# FT2232D.net
KiCad netlist of a schematic drawn in Altium Designer
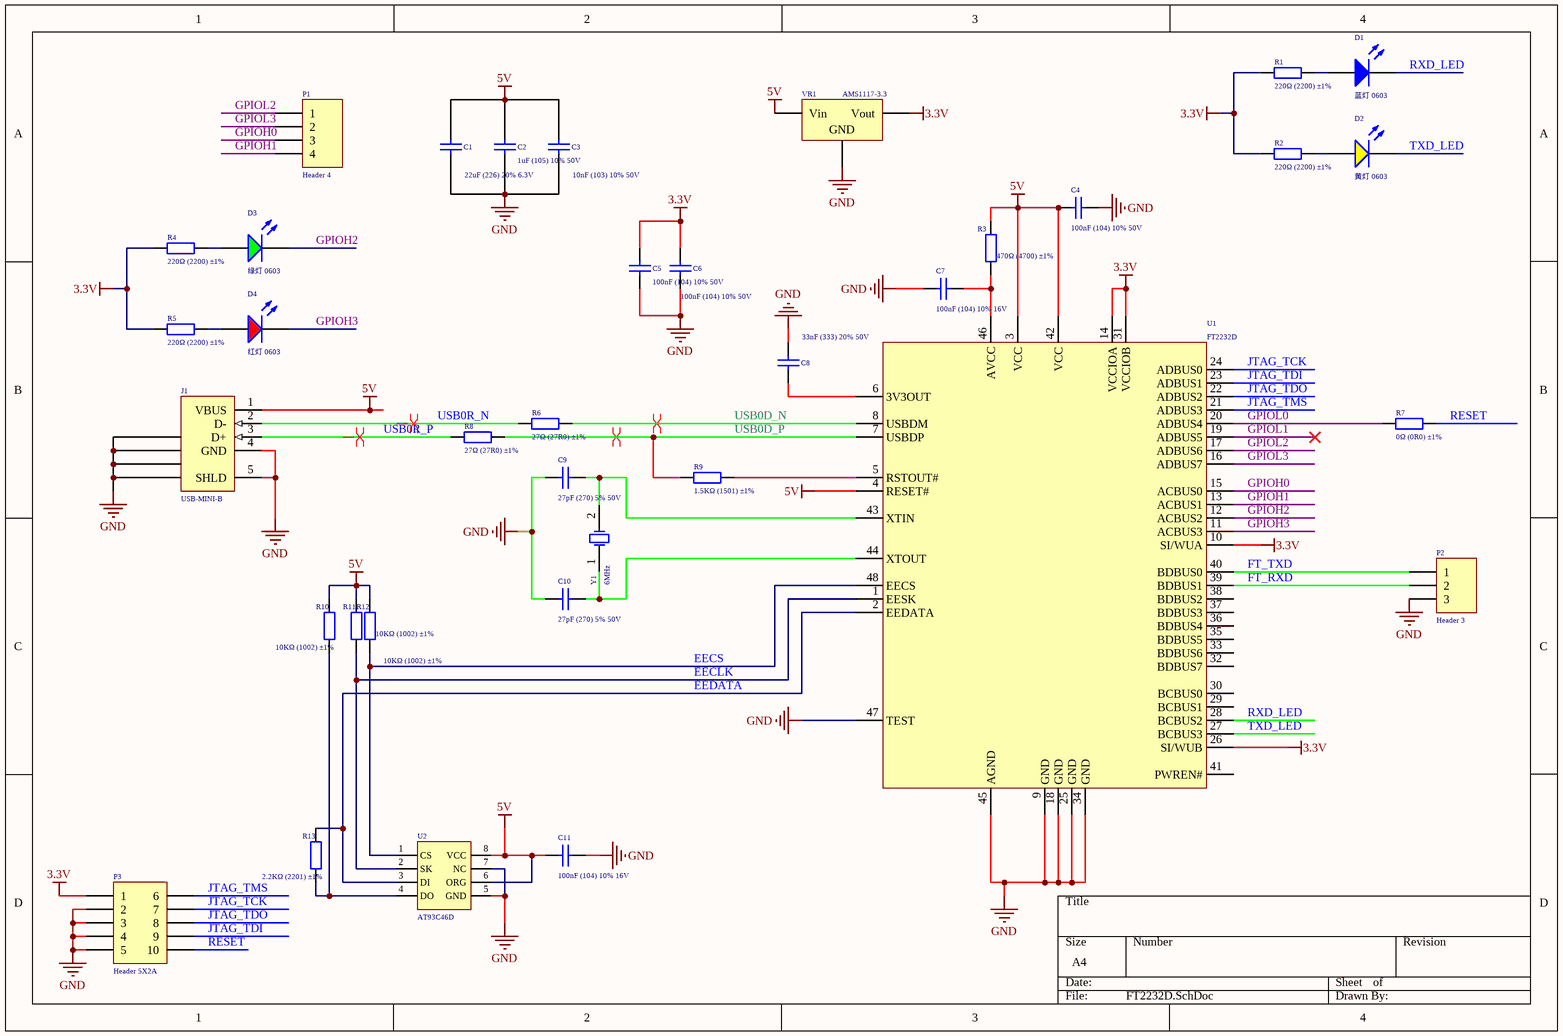
[diagram p0: FT2232D.SchDoc]

(export (version "E")
  (design (tool "Eeschema 10.0.6"))
  (components
    (comp (ref "C1")
      (value "22uF (226) 20% 6.3V")
      (footprint "0603_C")
      (description "贴片电容")
      (libsource (lib "Miscellaneous Devices LC") (part "0603 22uF (226) 20% 6.3V"))
    )
    (comp (ref "C2")
      (value "1uF (105) 10% 50V")
      (footprint "0603_C")
      (description "贴片电容")
      (libsource (lib "Miscellaneous Devices LC") (part "0603 1uF (105) 10% 50V"))
    )
    (comp (ref "C3")
      (value "10nF (103) 10% 50V")
      (footprint "0603_C")
      (description "贴片电容")
      (libsource (lib "Miscellaneous Devices LC") (part "0603 10nF (103) 10% 50V"))
    )
    (comp (ref "C4")
      (value "100nF (104) 10% 50V")
      (footprint "0603_C")
      (description "贴片电容")
      (libsource (lib "Miscellaneous Devices LC") (part "0603 100nF (104) 10% 50V"))
    )
    (comp (ref "C5")
      (value "100nF (104) 10% 50V")
      (footprint "0603_C")
      (description "贴片电容")
      (libsource (lib "Miscellaneous Devices LC") (part "0603 100nF (104) 10% 50V"))
    )
    (comp (ref "C6")
      (value "100nF (104) 10% 50V")
      (footprint "0603_C")
      (description "贴片电容")
      (libsource (lib "Miscellaneous Devices LC") (part "0603 100nF (104) 10% 50V"))
    )
    (comp (ref "C7")
      (value "100nF (104) 10% 16V")
      (footprint "0402_C")
      (description "贴片电容")
      (libsource (lib "Miscellaneous Devices LC") (part "0402 100nF (104) 10% 16V"))
    )
    (comp (ref "C8")
      (value "33nF (333) 20% 50V")
      (footprint "0402_C")
      (description "贴片电容")
      (libsource (lib "Miscellaneous Devices LC") (part "0402 33nF (333) 20% 50V"))
    )
    (comp (ref "C9")
      (value "27pF (270) 5% 50V")
      (footprint "0402_C")
      (description "贴片电容")
      (libsource (lib "Miscellaneous Devices LC") (part "0402 27pF (270) 5% 50V"))
    )
    (comp (ref "C10")
      (value "27pF (270) 5% 50V")
      (footprint "0402_C")
      (description "贴片电容")
      (libsource (lib "Miscellaneous Devices LC") (part "0402 27pF (270) 5% 50V"))
    )
    (comp (ref "C11")
      (value "100nF (104) 10% 16V")
      (footprint "0402_C")
      (description "贴片电容")
      (libsource (lib "Miscellaneous Devices LC") (part "0402 100nF (104) 10% 16V"))
    )
    (comp (ref "D1")
      (value "蓝灯 0603")
      (footprint "0603_LED_S1")
      (description "发光二极管")
      (libsource (lib "Miscellaneous Devices LC") (part "0603 蓝灯"))
    )
    (comp (ref "D2")
      (value "黄灯 0603")
      (footprint "0603_LED_S1")
      (description "发光二极管")
      (libsource (lib "Miscellaneous Devices LC") (part "0603 黄灯"))
    )
    (comp (ref "D3")
      (value "绿灯 0603")
      (footprint "0603_LED_S1")
      (description "发光二极管")
      (libsource (lib "Miscellaneous Devices LC") (part "0603 绿灯"))
    )
    (comp (ref "D4")
      (value "红灯 0603")
      (footprint "0603_LED_S1")
      (description "发光二极管")
      (libsource (lib "Miscellaneous Devices LC") (part "0603 红灯"))
    )
    (comp (ref "J1")
      (value "USB-MINI-B")
      (footprint "U-G-04WD-W-01 公头")
      (description "USB 2.0, Right Angle, SMT, A Type, Receptacle, 5 Position, Black")
      (fields (field (name "PUBLISHER") "Altium Limited"))
      (libsource (lib "Sparks") (part "USB-MINI-B"))
    )
    (comp (ref "P1")
      (value "Header 4")
      (footprint "HDR1X4")
      (description "Header, 4-Pin")
      (fields (field (name "PUBLISHER") "Altium Limited"))
      (libsource (lib "Sparks") (part "Header 4"))
    )
    (comp (ref "P2")
      (value "Header 3")
      (footprint "HDR1X3")
      (description "Header, 3-Pin")
      (fields (field (name "PUBLISHER") "Altium Limited"))
      (libsource (lib "Sparks") (part "Header 3"))
    )
    (comp (ref "P3")
      (value "Header 5X2A")
      (footprint "SMT HEADER 5*2")
      (description "Header, 5-Pin, Dual row")
      (fields (field (name "PUBLISHER") "Altium Limited"))
      (libsource (lib "Miscellaneous Connectors") (part "Header 5X2A"))
    )
    (comp (ref "R1")
      (value "220Ω (2200) ±1%")
      (footprint "0603_R")
      (description "贴片电阻")
      (libsource (lib "Miscellaneous Devices LC") (part "0603 220Ω (2200) 1%"))
    )
    (comp (ref "R2")
      (value "220Ω (2200) ±1%")
      (footprint "0603_R")
      (description "贴片电阻")
      (libsource (lib "Miscellaneous Devices LC") (part "0603 220Ω (2200) 1%"))
    )
    (comp (ref "R3")
      (value "470Ω (4700) ±1%")
      (footprint "0402_R")
      (description "贴片电阻")
      (libsource (lib "Miscellaneous Devices LC") (part "0402 470Ω (4700) 1%"))
    )
    (comp (ref "R4")
      (value "220Ω (2200) ±1%")
      (footprint "0402_R")
      (description "贴片电阻")
      (libsource (lib "Miscellaneous Devices LC") (part "0402 220Ω (2200) 1%"))
    )
    (comp (ref "R5")
      (value "220Ω (2200) ±1%")
      (footprint "0402_R")
      (description "贴片电阻")
      (libsource (lib "Miscellaneous Devices LC") (part "0402 220Ω (2200) 1%"))
    )
    (comp (ref "R6")
      (value "27Ω (27R0) ±1%")
      (footprint "0603_R")
      (description "贴片电阻")
      (libsource (lib "Miscellaneous Devices LC") (part "0603 27Ω (27R0) 1%"))
    )
    (comp (ref "R7")
      (value "0Ω (0R0) ±1%")
      (footprint "0402_R")
      (description "贴片电阻")
      (libsource (lib "Miscellaneous Devices LC") (part "0402 0Ω (0R0) 1%"))
    )
    (comp (ref "R8")
      (value "27Ω (27R0) ±1%")
      (footprint "0603_R")
      (description "贴片电阻")
      (libsource (lib "Miscellaneous Devices LC") (part "0603 27Ω (27R0) 1%"))
    )
    (comp (ref "R9")
      (value "1.5KΩ (1501) ±1%")
      (footprint "0402_R")
      (description "贴片电阻")
      (libsource (lib "Miscellaneous Devices LC") (part "0402 1.5KΩ (1501) 1%"))
    )
    (comp (ref "R10")
      (value "10KΩ (1002) ±1%")
      (footprint "0402_R")
      (description "贴片电阻")
      (libsource (lib "Miscellaneous Devices LC") (part "0402 10KΩ (1002) 1%"))
    )
    (comp (ref "R11")
      (value "10KΩ (1002) ±1%")
      (footprint "0402_R")
      (description "贴片电阻")
      (libsource (lib "Miscellaneous Devices LC") (part "0402 10KΩ (1002) 1%"))
    )
    (comp (ref "R12")
      (value "10KΩ (1002) ±1%")
      (footprint "0402_R")
      (description "贴片电阻")
      (libsource (lib "Miscellaneous Devices LC") (part "0402 10KΩ (1002) 1%"))
    )
    (comp (ref "R13")
      (value "2.2KΩ (2201) ±1%")
      (footprint "0402_R")
      (description "贴片电阻")
      (libsource (lib "Miscellaneous Devices LC") (part "0402 2.2KΩ (2201) 1%"))
    )
    (comp (ref "U1")
      (value "FT2232D")
      (footprint "LC-LQFP-48_7x7x05P")
      (libsource (lib "2号库") (part "FT2232D"))
    )
    (comp (ref "U2")
      (value "AT93C46D")
      (footprint "LC-SOIC-8_150mil")
      (libsource (lib "2号库") (part "AT93C46D"))
    )
    (comp (ref "VR1")
      (value "AMS1117-3.3")
      (footprint "SOT-223")
      (description "低压差线性稳压(LDO)")
      (libsource (lib "Miscellaneous Devices LC") (part "SOT-223 AMS1117-3.3"))
    )
    (comp (ref "Y1")
      (value "6MHz")
      (footprint "XTAL-RAD-0.2")
      (description "晶体振荡器")
      (fields (field (name "PUBLISHER") "Altium Limited"))
      (libsource (lib "Sparks") (part "XTAL"))
    )
  )
  (nets
    (net (code "1") (name "/EECLK") (class "Default")
      (node (ref "R11") (pin "1") (pinfunction "1_1") (pintype "passive"))
      (node (ref "U1") (pin "1") (pinfunction "EESK_1") (pintype "passive"))
      (node (ref "U2") (pin "2") (pinfunction "SK_2") (pintype "passive"))
    )
    (net (code "2") (name "/EECS") (class "Default")
      (node (ref "R12") (pin "1") (pinfunction "1_1") (pintype "passive"))
      (node (ref "U1") (pin "48") (pinfunction "EECS_48") (pintype "passive"))
      (node (ref "U2") (pin "1") (pinfunction "CS_1") (pintype "passive"))
    )
    (net (code "3") (name "/EEDATA") (class "Default")
      (node (ref "R13") (pin "2") (pinfunction "2_2") (pintype "passive"))
      (node (ref "U1") (pin "2") (pinfunction "EEDATA_2") (pintype "passive"))
      (node (ref "U2") (pin "3") (pinfunction "DI_3") (pintype "passive"))
    )
    (net (code "4") (name "/FT_RXD") (class "Default")
      (node (ref "P2") (pin "2") (pinfunction "2_2") (pintype "passive"))
      (node (ref "U1") (pin "39") (pinfunction "BDBUS1_39") (pintype "passive"))
    )
    (net (code "5") (name "/FT_TXD") (class "Default")
      (node (ref "P2") (pin "1") (pinfunction "1_1") (pintype "passive"))
      (node (ref "U1") (pin "40") (pinfunction "BDBUS0_40") (pintype "passive"))
    )
    (net (code "6") (name "/GPIOH0") (class "Default")
      (node (ref "P1") (pin "3") (pinfunction "3_3") (pintype "passive"))
      (node (ref "U1") (pin "15") (pinfunction "ACBUS0_15") (pintype "passive"))
    )
    (net (code "7") (name "/GPIOH1") (class "Default")
      (node (ref "P1") (pin "4") (pinfunction "4_4") (pintype "passive"))
      (node (ref "U1") (pin "13") (pinfunction "ACBUS1_13") (pintype "passive"))
    )
    (net (code "8") (name "/GPIOH2") (class "Default")
      (node (ref "D3") (pin "K") (pinfunction "K_K") (pintype "passive"))
      (node (ref "U1") (pin "12") (pinfunction "ACBUS2_12") (pintype "passive"))
    )
    (net (code "9") (name "/GPIOH3") (class "Default")
      (node (ref "D4") (pin "K") (pinfunction "K_K") (pintype "passive"))
      (node (ref "U1") (pin "11") (pinfunction "ACBUS3_11") (pintype "passive"))
    )
    (net (code "10") (name "/GPIOL0") (class "Default")
      (node (ref "R7") (pin "1") (pinfunction "1_1") (pintype "passive"))
      (node (ref "U1") (pin "20") (pinfunction "ADBUS4_20") (pintype "passive"))
    )
    (net (code "11") (name "/GPIOL1") (class "Default")
      (node (ref "U1") (pin "19") (pinfunction "ADBUS5_19") (pintype "passive+no_connect"))
    )
    (net (code "12") (name "/GPIOL2") (class "Default")
      (node (ref "P1") (pin "1") (pinfunction "1_1") (pintype "passive"))
      (node (ref "U1") (pin "17") (pinfunction "ADBUS6_17") (pintype "passive"))
    )
    (net (code "13") (name "/GPIOL3") (class "Default")
      (node (ref "P1") (pin "2") (pinfunction "2_2") (pintype "passive"))
      (node (ref "U1") (pin "16") (pinfunction "ADBUS7_16") (pintype "passive"))
    )
    (net (code "14") (name "/JTAG_TCK") (class "Default")
      (node (ref "P3") (pin "7") (pinfunction "7_7") (pintype "passive"))
      (node (ref "U1") (pin "24") (pinfunction "ADBUS0_24") (pintype "passive"))
    )
    (net (code "15") (name "/JTAG_TDI") (class "Default")
      (node (ref "P3") (pin "9") (pinfunction "9_9") (pintype "passive"))
      (node (ref "U1") (pin "23") (pinfunction "ADBUS1_23") (pintype "passive"))
    )
    (net (code "16") (name "/JTAG_TDO") (class "Default")
      (node (ref "P3") (pin "8") (pinfunction "8_8") (pintype "passive"))
      (node (ref "U1") (pin "22") (pinfunction "ADBUS2_22") (pintype "passive"))
    )
    (net (code "17") (name "/JTAG_TMS") (class "Default")
      (node (ref "P3") (pin "6") (pinfunction "6_6") (pintype "passive"))
      (node (ref "U1") (pin "21") (pinfunction "ADBUS3_21") (pintype "passive"))
    )
    (net (code "18") (name "/RESET") (class "Default")
      (node (ref "P3") (pin "10") (pinfunction "10_10") (pintype "passive"))
      (node (ref "R7") (pin "2") (pinfunction "2_2") (pintype "passive"))
    )
    (net (code "19") (name "/RXD_LED") (class "Default")
      (node (ref "D1") (pin "K") (pinfunction "K_K") (pintype "passive"))
      (node (ref "U1") (pin "28") (pinfunction "BCBUS2_28") (pintype "passive"))
    )
    (net (code "20") (name "/TXD_LED") (class "Default")
      (node (ref "D2") (pin "K") (pinfunction "K_K") (pintype "passive"))
      (node (ref "U1") (pin "27") (pinfunction "BCBUS3_27") (pintype "passive"))
    )
    (net (code "21") (name "/USB0D_N") (class "Default")
      (node (ref "R6") (pin "2") (pinfunction "2_2") (pintype "passive"))
      (node (ref "U1") (pin "8") (pinfunction "USBDM_8") (pintype "passive"))
    )
    (net (code "22") (name "/USB0D_P") (class "Default")
      (node (ref "R8") (pin "2") (pinfunction "2_2") (pintype "passive"))
      (node (ref "R9") (pin "1") (pinfunction "1_1") (pintype "passive"))
      (node (ref "U1") (pin "7") (pinfunction "USBDP_7") (pintype "passive"))
    )
    (net (code "23") (name "/USB0R_N") (class "Default")
      (node (ref "J1") (pin "2") (pinfunction "D-_2") (pintype "input"))
      (node (ref "R6") (pin "1") (pinfunction "1_1") (pintype "passive"))
    )
    (net (code "24") (name "/USB0R_P") (class "Default")
      (node (ref "J1") (pin "3") (pinfunction "D+_3") (pintype "input"))
      (node (ref "R8") (pin "1") (pinfunction "1_1") (pintype "passive"))
    )
    (net (code "25") (name "3.3V") (class "Default")
      (node (ref "C5") (pin "2") (pinfunction "2_2") (pintype "passive"))
      (node (ref "C6") (pin "2") (pinfunction "2_2") (pintype "passive"))
      (node (ref "P3") (pin "1") (pinfunction "1_1") (pintype "passive"))
      (node (ref "R1") (pin "1") (pinfunction "1_1") (pintype "passive"))
      (node (ref "R2") (pin "1") (pinfunction "1_1") (pintype "passive"))
      (node (ref "R4") (pin "1") (pinfunction "1_1") (pintype "passive"))
      (node (ref "R5") (pin "1") (pinfunction "1_1") (pintype "passive"))
      (node (ref "U1") (pin "10") (pinfunction "SI/WUA_10") (pintype "passive"))
      (node (ref "U1") (pin "14") (pinfunction "VCCIOA_14") (pintype "passive"))
      (node (ref "U1") (pin "26") (pinfunction "SI/WUB_26") (pintype "passive"))
      (node (ref "U1") (pin "31") (pinfunction "VCCIOB_31") (pintype "passive"))
      (node (ref "VR1") (pin "2") (pinfunction "Vout_2") (pintype "passive"))
    )
    (net (code "26") (name "5V") (class "Default")
      (node (ref "C1") (pin "1") (pinfunction "1_1") (pintype "passive"))
      (node (ref "C11") (pin "1") (pinfunction "1_1") (pintype "passive"))
      (node (ref "C2") (pin "1") (pinfunction "1_1") (pintype "passive"))
      (node (ref "C3") (pin "1") (pinfunction "1_1") (pintype "passive"))
      (node (ref "C4") (pin "1") (pinfunction "1_1") (pintype "passive"))
      (node (ref "J1") (pin "1") (pinfunction "VBUS_1") (pintype "power_in"))
      (node (ref "R10") (pin "2") (pinfunction "2_2") (pintype "passive"))
      (node (ref "R11") (pin "2") (pinfunction "2_2") (pintype "passive"))
      (node (ref "R12") (pin "2") (pinfunction "2_2") (pintype "passive"))
      (node (ref "R3") (pin "2") (pinfunction "2_2") (pintype "passive"))
      (node (ref "U1") (pin "3") (pinfunction "VCC_3") (pintype "passive"))
      (node (ref "U1") (pin "4") (pinfunction "RESET#_4") (pintype "passive"))
      (node (ref "U1") (pin "42") (pinfunction "VCC_42") (pintype "passive"))
      (node (ref "U2") (pin "6") (pinfunction "ORG_6") (pintype "passive"))
      (node (ref "U2") (pin "8") (pinfunction "VCC_8") (pintype "passive"))
      (node (ref "VR1") (pin "3") (pinfunction "Vin_3") (pintype "passive"))
    )
    (net (code "27") (name "GND") (class "Default")
      (node (ref "C1") (pin "2") (pinfunction "2_2") (pintype "passive"))
      (node (ref "C10") (pin "1") (pinfunction "1_1") (pintype "passive"))
      (node (ref "C11") (pin "2") (pinfunction "2_2") (pintype "passive"))
      (node (ref "C2") (pin "2") (pinfunction "2_2") (pintype "passive"))
      (node (ref "C3") (pin "2") (pinfunction "2_2") (pintype "passive"))
      (node (ref "C4") (pin "2") (pinfunction "2_2") (pintype "passive"))
      (node (ref "C5") (pin "1") (pinfunction "1_1") (pintype "passive"))
      (node (ref "C6") (pin "1") (pinfunction "1_1") (pintype "passive"))
      (node (ref "C7") (pin "1") (pinfunction "1_1") (pintype "passive"))
      (node (ref "C8") (pin "2") (pinfunction "2_2") (pintype "passive"))
      (node (ref "C9") (pin "1") (pinfunction "1_1") (pintype "passive"))
      (node (ref "J1") (pin "4") (pinfunction "GND_4") (pintype "power_in"))
      (node (ref "J1") (pin "5") (pinfunction "SHLD_5") (pintype "passive"))
      (node (ref "J1") (pin "6") (pinfunction "SHLD_6") (pintype "passive"))
      (node (ref "J1") (pin "7") (pinfunction "SHLD_7") (pintype "passive"))
      (node (ref "J1") (pin "8") (pinfunction "SHLD_8") (pintype "passive"))
      (node (ref "J1") (pin "9") (pinfunction "SHLD_9") (pintype "passive"))
      (node (ref "P2") (pin "3") (pinfunction "3_3") (pintype "passive"))
      (node (ref "P3") (pin "2") (pinfunction "2_2") (pintype "passive"))
      (node (ref "P3") (pin "3") (pinfunction "3_3") (pintype "passive"))
      (node (ref "P3") (pin "4") (pinfunction "4_4") (pintype "passive"))
      (node (ref "P3") (pin "5") (pinfunction "5_5") (pintype "passive"))
      (node (ref "U1") (pin "18") (pinfunction "GND_18") (pintype "passive"))
      (node (ref "U1") (pin "25") (pinfunction "GND_25") (pintype "passive"))
      (node (ref "U1") (pin "34") (pinfunction "GND_34") (pintype "passive"))
      (node (ref "U1") (pin "45") (pinfunction "AGND_45") (pintype "passive"))
      (node (ref "U1") (pin "47") (pinfunction "TEST_47") (pintype "passive"))
      (node (ref "U1") (pin "9") (pinfunction "GND_9") (pintype "passive"))
      (node (ref "U2") (pin "5") (pinfunction "GND_5") (pintype "passive"))
      (node (ref "U2") (pin "7") (pinfunction "NC_7") (pintype "passive"))
      (node (ref "VR1") (pin "1") (pinfunction "GND_1") (pintype "passive"))
    )
    (net (code "28") (name "Net-(D1-PadA)") (class "Default")
      (node (ref "D1") (pin "A") (pinfunction "A_A") (pintype "passive"))
      (node (ref "R1") (pin "2") (pinfunction "2_2") (pintype "passive"))
    )
    (net (code "29") (name "Net-(D2-PadA)") (class "Default")
      (node (ref "D2") (pin "A") (pinfunction "A_A") (pintype "passive"))
      (node (ref "R2") (pin "2") (pinfunction "2_2") (pintype "passive"))
    )
    (net (code "30") (name "Net-(D3-PadA)") (class "Default")
      (node (ref "D3") (pin "A") (pinfunction "A_A") (pintype "passive"))
      (node (ref "R4") (pin "2") (pinfunction "2_2") (pintype "passive"))
    )
    (net (code "31") (name "Net-(D4-PadA)") (class "Default")
      (node (ref "D4") (pin "A") (pinfunction "A_A") (pintype "passive"))
      (node (ref "R5") (pin "2") (pinfunction "2_2") (pintype "passive"))
    )
    (net (code "32") (name "Net-(U1-3V3OUT)") (class "Default")
      (node (ref "C8") (pin "1") (pinfunction "1_1") (pintype "passive"))
      (node (ref "U1") (pin "6") (pinfunction "3V3OUT_6") (pintype "passive"))
    )
    (net (code "33") (name "Net-(U1-AVCC)") (class "Default")
      (node (ref "C7") (pin "2") (pinfunction "2_2") (pintype "passive"))
      (node (ref "R3") (pin "1") (pinfunction "1_1") (pintype "passive"))
      (node (ref "U1") (pin "46") (pinfunction "AVCC_46") (pintype "passive"))
    )
    (net (code "34") (name "Net-(U1-RSTOUT#)") (class "Default")
      (node (ref "R9") (pin "2") (pinfunction "2_2") (pintype "passive"))
      (node (ref "U1") (pin "5") (pinfunction "RSTOUT#_5") (pintype "passive"))
    )
    (net (code "35") (name "Net-(U1-XTIN)") (class "Default")
      (node (ref "C9") (pin "2") (pinfunction "2_2") (pintype "passive"))
      (node (ref "U1") (pin "43") (pinfunction "XTIN_43") (pintype "passive"))
      (node (ref "Y1") (pin "2") (pinfunction "OSC2_2") (pintype "passive"))
    )
    (net (code "36") (name "Net-(U1-XTOUT)") (class "Default")
      (node (ref "C10") (pin "2") (pinfunction "2_2") (pintype "passive"))
      (node (ref "U1") (pin "44") (pinfunction "XTOUT_44") (pintype "passive"))
      (node (ref "Y1") (pin "1") (pinfunction "OSC1_1") (pintype "passive"))
    )
    (net (code "37") (name "Net-(U2-DO)") (class "Default")
      (node (ref "R10") (pin "1") (pinfunction "1_1") (pintype "passive"))
      (node (ref "R13") (pin "1") (pinfunction "1_1") (pintype "passive"))
      (node (ref "U2") (pin "4") (pinfunction "DO_4") (pintype "passive"))
    )
    (net (code "38") (name "unconnected-(U1-BCBUS0-Pad30)") (class "Default")
      (node (ref "U1") (pin "30") (pinfunction "BCBUS0_30") (pintype "passive"))
    )
    (net (code "39") (name "unconnected-(U1-BCBUS1-Pad29)") (class "Default")
      (node (ref "U1") (pin "29") (pinfunction "BCBUS1_29") (pintype "passive"))
    )
    (net (code "40") (name "unconnected-(U1-BDBUS2-Pad38)") (class "Default")
      (node (ref "U1") (pin "38") (pinfunction "BDBUS2_38") (pintype "passive"))
    )
    (net (code "41") (name "unconnected-(U1-BDBUS3-Pad37)") (class "Default")
      (node (ref "U1") (pin "37") (pinfunction "BDBUS3_37") (pintype "passive"))
    )
    (net (code "42") (name "unconnected-(U1-BDBUS4-Pad36)") (class "Default")
      (node (ref "U1") (pin "36") (pinfunction "BDBUS4_36") (pintype "passive"))
    )
    (net (code "43") (name "unconnected-(U1-BDBUS5-Pad35)") (class "Default")
      (node (ref "U1") (pin "35") (pinfunction "BDBUS5_35") (pintype "passive"))
    )
    (net (code "44") (name "unconnected-(U1-BDBUS6-Pad33)") (class "Default")
      (node (ref "U1") (pin "33") (pinfunction "BDBUS6_33") (pintype "passive"))
    )
    (net (code "45") (name "unconnected-(U1-BDBUS7-Pad32)") (class "Default")
      (node (ref "U1") (pin "32") (pinfunction "BDBUS7_32") (pintype "passive"))
    )
    (net (code "46") (name "unconnected-(U1-PWREN#-Pad41)") (class "Default")
      (node (ref "U1") (pin "41") (pinfunction "PWREN#_41") (pintype "passive"))
    )
  )
)
